# INJ4SS.net
KiCad netlist of a schematic drawn in EAGLE
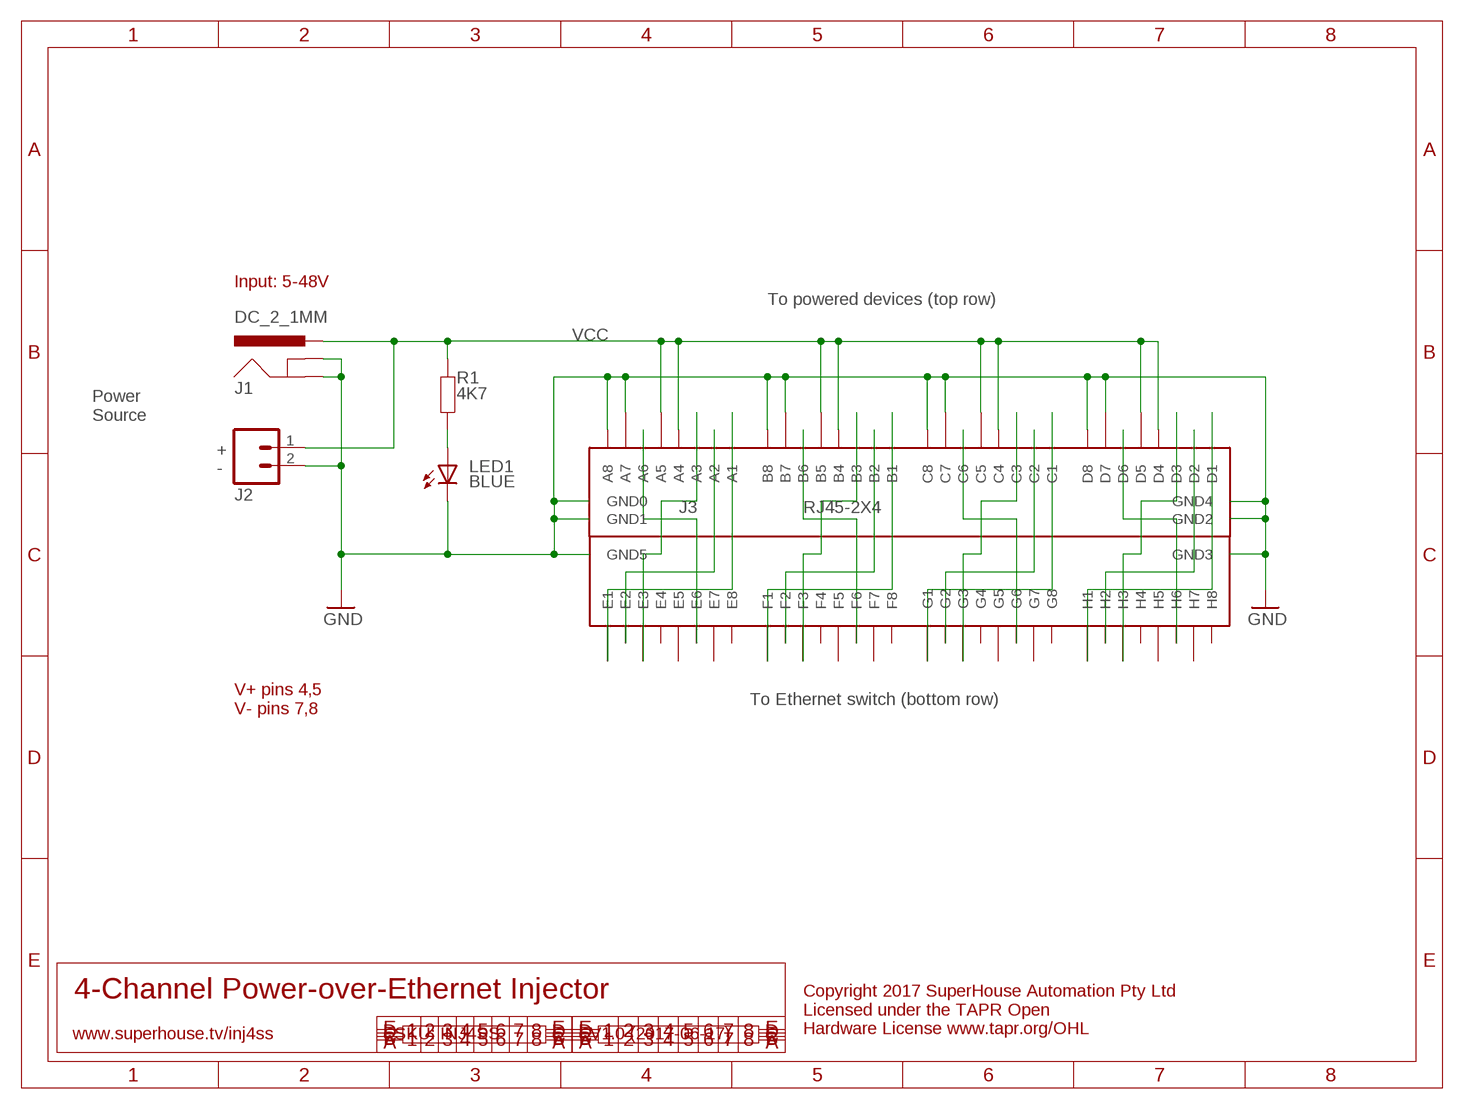
[diagram p0: schematic, sheet 1]

(export (version "E")
  (design (tool "Eeschema 10.0.6"))
  (components
    (comp (ref "J1")
      (value "DC_2_1MM")
      (footprint "eagle-import:POWER_JACK_PTH")
      (libsource (lib "eagle-import") (part "POWER_JACKPTH"))
    )
    (comp (ref "J2")
      (value "M023.5MM")
      (footprint "eagle-import:SCREWTERMINAL-3.5MM-2")
      (libsource (lib "eagle-import") (part "M023.5MM"))
    )
    (comp (ref "J3")
      (value "RJ45-2X4")
      (footprint "eagle-import:RJ45-2X4")
      (libsource (lib "eagle-import") (part "RJ45-2X4"))
    )
    (comp (ref "LED1")
      (value "BLUE")
      (footprint "eagle-import:LED3MM")
      (libsource (lib "eagle-import") (part "LED3MM"))
    )
    (comp (ref "R1")
      (value "4K7")
      (footprint "eagle-import:RES-4")
      (libsource (lib "eagle-import") (part "RESISTORPTH4"))
    )
  )
  (nets
    (net (code "1") (name "/VCC") (class "Default")
      (node (ref "J1") (pin "PWR") (pinfunction "PWR_PWR") (pintype "bidirectional"))
      (node (ref "J2") (pin "1") (pinfunction "1_1") (pintype "passive"))
      (node (ref "J3") (pin "A4") (pinfunction "A4_A4") (pintype "bidirectional"))
      (node (ref "J3") (pin "A5") (pinfunction "A5_A5") (pintype "bidirectional"))
      (node (ref "J3") (pin "B4") (pinfunction "B4_B4") (pintype "bidirectional"))
      (node (ref "J3") (pin "B5") (pinfunction "B5_B5") (pintype "bidirectional"))
      (node (ref "J3") (pin "C4") (pinfunction "C4_C4") (pintype "bidirectional"))
      (node (ref "J3") (pin "C5") (pinfunction "C5_C5") (pintype "bidirectional"))
      (node (ref "J3") (pin "D4") (pinfunction "D4_D4") (pintype "bidirectional"))
      (node (ref "J3") (pin "D5") (pinfunction "D5_D5") (pintype "bidirectional"))
      (node (ref "R1") (pin "1") (pinfunction "1_1") (pintype "passive"))
    )
    (net (code "2") (name "GND") (class "Default")
      (node (ref "J1") (pin "GND") (pinfunction "GND_GND") (pintype "bidirectional"))
      (node (ref "J1") (pin "GNDBREAK") (pinfunction "GNDBREAK_GNDBREAK") (pintype "bidirectional"))
      (node (ref "J2") (pin "2") (pinfunction "2_2") (pintype "passive"))
      (node (ref "J3") (pin "A7") (pinfunction "A7_A7") (pintype "bidirectional"))
      (node (ref "J3") (pin "A8") (pinfunction "A8_A8") (pintype "bidirectional"))
      (node (ref "J3") (pin "B7") (pinfunction "B7_B7") (pintype "bidirectional"))
      (node (ref "J3") (pin "B8") (pinfunction "B8_B8") (pintype "bidirectional"))
      (node (ref "J3") (pin "C7") (pinfunction "C7_C7") (pintype "bidirectional"))
      (node (ref "J3") (pin "C8") (pinfunction "C8_C8") (pintype "bidirectional"))
      (node (ref "J3") (pin "D7") (pinfunction "D7_D7") (pintype "bidirectional"))
      (node (ref "J3") (pin "D8") (pinfunction "D8_D8") (pintype "bidirectional"))
      (node (ref "J3") (pin "GND0") (pinfunction "GND0_GND0") (pintype "power_in"))
      (node (ref "J3") (pin "GND1") (pinfunction "GND1_GND1") (pintype "power_in"))
      (node (ref "J3") (pin "GND2") (pinfunction "GND2_GND2") (pintype "power_in"))
      (node (ref "J3") (pin "GND3") (pinfunction "GND3_GND3") (pintype "power_in"))
      (node (ref "J3") (pin "GND4") (pinfunction "GND4_GND4") (pintype "power_in"))
      (node (ref "J3") (pin "GND5") (pinfunction "GND5_GND5") (pintype "power_in"))
      (node (ref "LED1") (pin "K") (pinfunction "C_K") (pintype "passive"))
    )
    (net (code "3") (name "Net-(J3-PadA1)") (class "Default")
      (node (ref "J3") (pin "A1") (pinfunction "A1_A1") (pintype "bidirectional"))
      (node (ref "J3") (pin "E1") (pinfunction "E1_E1") (pintype "bidirectional"))
    )
    (net (code "4") (name "Net-(J3-PadA2)") (class "Default")
      (node (ref "J3") (pin "A2") (pinfunction "A2_A2") (pintype "bidirectional"))
      (node (ref "J3") (pin "E2") (pinfunction "E2_E2") (pintype "bidirectional"))
    )
    (net (code "5") (name "Net-(J3-PadA3)") (class "Default")
      (node (ref "J3") (pin "A3") (pinfunction "A3_A3") (pintype "bidirectional"))
      (node (ref "J3") (pin "E3") (pinfunction "E3_E3") (pintype "bidirectional"))
    )
    (net (code "6") (name "Net-(J3-PadA6)") (class "Default")
      (node (ref "J3") (pin "A6") (pinfunction "A6_A6") (pintype "bidirectional"))
      (node (ref "J3") (pin "E6") (pinfunction "E6_E6") (pintype "bidirectional"))
    )
    (net (code "7") (name "Net-(J3-PadB1)") (class "Default")
      (node (ref "J3") (pin "B1") (pinfunction "B1_B1") (pintype "bidirectional"))
      (node (ref "J3") (pin "F1") (pinfunction "F1_F1") (pintype "bidirectional"))
    )
    (net (code "8") (name "Net-(J3-PadB2)") (class "Default")
      (node (ref "J3") (pin "B2") (pinfunction "B2_B2") (pintype "bidirectional"))
      (node (ref "J3") (pin "F2") (pinfunction "F2_F2") (pintype "bidirectional"))
    )
    (net (code "9") (name "Net-(J3-PadB3)") (class "Default")
      (node (ref "J3") (pin "B3") (pinfunction "B3_B3") (pintype "bidirectional"))
      (node (ref "J3") (pin "F3") (pinfunction "F3_F3") (pintype "bidirectional"))
    )
    (net (code "10") (name "Net-(J3-PadB6)") (class "Default")
      (node (ref "J3") (pin "B6") (pinfunction "B6_B6") (pintype "bidirectional"))
      (node (ref "J3") (pin "F6") (pinfunction "F6_F6") (pintype "bidirectional"))
    )
    (net (code "11") (name "Net-(J3-PadC1)") (class "Default")
      (node (ref "J3") (pin "C1") (pinfunction "C1_C1") (pintype "bidirectional"))
      (node (ref "J3") (pin "G1") (pinfunction "G1_G1") (pintype "bidirectional"))
    )
    (net (code "12") (name "Net-(J3-PadC2)") (class "Default")
      (node (ref "J3") (pin "C2") (pinfunction "C2_C2") (pintype "bidirectional"))
      (node (ref "J3") (pin "G2") (pinfunction "G2_G2") (pintype "bidirectional"))
    )
    (net (code "13") (name "Net-(J3-PadC3)") (class "Default")
      (node (ref "J3") (pin "C3") (pinfunction "C3_C3") (pintype "bidirectional"))
      (node (ref "J3") (pin "G3") (pinfunction "G3_G3") (pintype "bidirectional"))
    )
    (net (code "14") (name "Net-(J3-PadC6)") (class "Default")
      (node (ref "J3") (pin "C6") (pinfunction "C6_C6") (pintype "bidirectional"))
      (node (ref "J3") (pin "G6") (pinfunction "G6_G6") (pintype "bidirectional"))
    )
    (net (code "15") (name "Net-(J3-PadD1)") (class "Default")
      (node (ref "J3") (pin "D1") (pinfunction "D1_D1") (pintype "bidirectional"))
      (node (ref "J3") (pin "H1") (pinfunction "H1_H1") (pintype "bidirectional"))
    )
    (net (code "16") (name "Net-(J3-PadD2)") (class "Default")
      (node (ref "J3") (pin "D2") (pinfunction "D2_D2") (pintype "bidirectional"))
      (node (ref "J3") (pin "H2") (pinfunction "H2_H2") (pintype "bidirectional"))
    )
    (net (code "17") (name "Net-(J3-PadD3)") (class "Default")
      (node (ref "J3") (pin "D3") (pinfunction "D3_D3") (pintype "bidirectional"))
      (node (ref "J3") (pin "H3") (pinfunction "H3_H3") (pintype "bidirectional"))
    )
    (net (code "18") (name "Net-(J3-PadD6)") (class "Default")
      (node (ref "J3") (pin "D6") (pinfunction "D6_D6") (pintype "bidirectional"))
      (node (ref "J3") (pin "H6") (pinfunction "H6_H6") (pintype "bidirectional"))
    )
    (net (code "19") (name "Net-(LED1-PadA)") (class "Default")
      (node (ref "LED1") (pin "A") (pinfunction "A_A") (pintype "passive"))
      (node (ref "R1") (pin "2") (pinfunction "2_2") (pintype "passive"))
    )
    (net (code "20") (name "unconnected-(J3-PadE4)") (class "Default")
      (node (ref "J3") (pin "E4") (pinfunction "E4_E4") (pintype "bidirectional"))
    )
    (net (code "21") (name "unconnected-(J3-PadE5)") (class "Default")
      (node (ref "J3") (pin "E5") (pinfunction "E5_E5") (pintype "bidirectional"))
    )
    (net (code "22") (name "unconnected-(J3-PadE7)") (class "Default")
      (node (ref "J3") (pin "E7") (pinfunction "E7_E7") (pintype "bidirectional"))
    )
    (net (code "23") (name "unconnected-(J3-PadE8)") (class "Default")
      (node (ref "J3") (pin "E8") (pinfunction "E8_E8") (pintype "bidirectional"))
    )
    (net (code "24") (name "unconnected-(J3-PadF4)") (class "Default")
      (node (ref "J3") (pin "F4") (pinfunction "F4_F4") (pintype "bidirectional"))
    )
    (net (code "25") (name "unconnected-(J3-PadF5)") (class "Default")
      (node (ref "J3") (pin "F5") (pinfunction "F5_F5") (pintype "bidirectional"))
    )
    (net (code "26") (name "unconnected-(J3-PadF7)") (class "Default")
      (node (ref "J3") (pin "F7") (pinfunction "F7_F7") (pintype "bidirectional"))
    )
    (net (code "27") (name "unconnected-(J3-PadF8)") (class "Default")
      (node (ref "J3") (pin "F8") (pinfunction "F8_F8") (pintype "bidirectional"))
    )
    (net (code "28") (name "unconnected-(J3-PadG4)") (class "Default")
      (node (ref "J3") (pin "G4") (pinfunction "G4_G4") (pintype "bidirectional"))
    )
    (net (code "29") (name "unconnected-(J3-PadG5)") (class "Default")
      (node (ref "J3") (pin "G5") (pinfunction "G5_G5") (pintype "bidirectional"))
    )
    (net (code "30") (name "unconnected-(J3-PadG7)") (class "Default")
      (node (ref "J3") (pin "G7") (pinfunction "G7_G7") (pintype "bidirectional"))
    )
    (net (code "31") (name "unconnected-(J3-PadG8)") (class "Default")
      (node (ref "J3") (pin "G8") (pinfunction "G8_G8") (pintype "bidirectional"))
    )
    (net (code "32") (name "unconnected-(J3-PadH4)") (class "Default")
      (node (ref "J3") (pin "H4") (pinfunction "H4_H4") (pintype "bidirectional"))
    )
    (net (code "33") (name "unconnected-(J3-PadH5)") (class "Default")
      (node (ref "J3") (pin "H5") (pinfunction "H5_H5") (pintype "bidirectional"))
    )
    (net (code "34") (name "unconnected-(J3-PadH7)") (class "Default")
      (node (ref "J3") (pin "H7") (pinfunction "H7_H7") (pintype "bidirectional"))
    )
    (net (code "35") (name "unconnected-(J3-PadH8)") (class "Default")
      (node (ref "J3") (pin "H8") (pinfunction "H8_H8") (pintype "bidirectional"))
    )
  )
)
